# boards.net
KiCad netlist of a schematic drawn in EAGLE
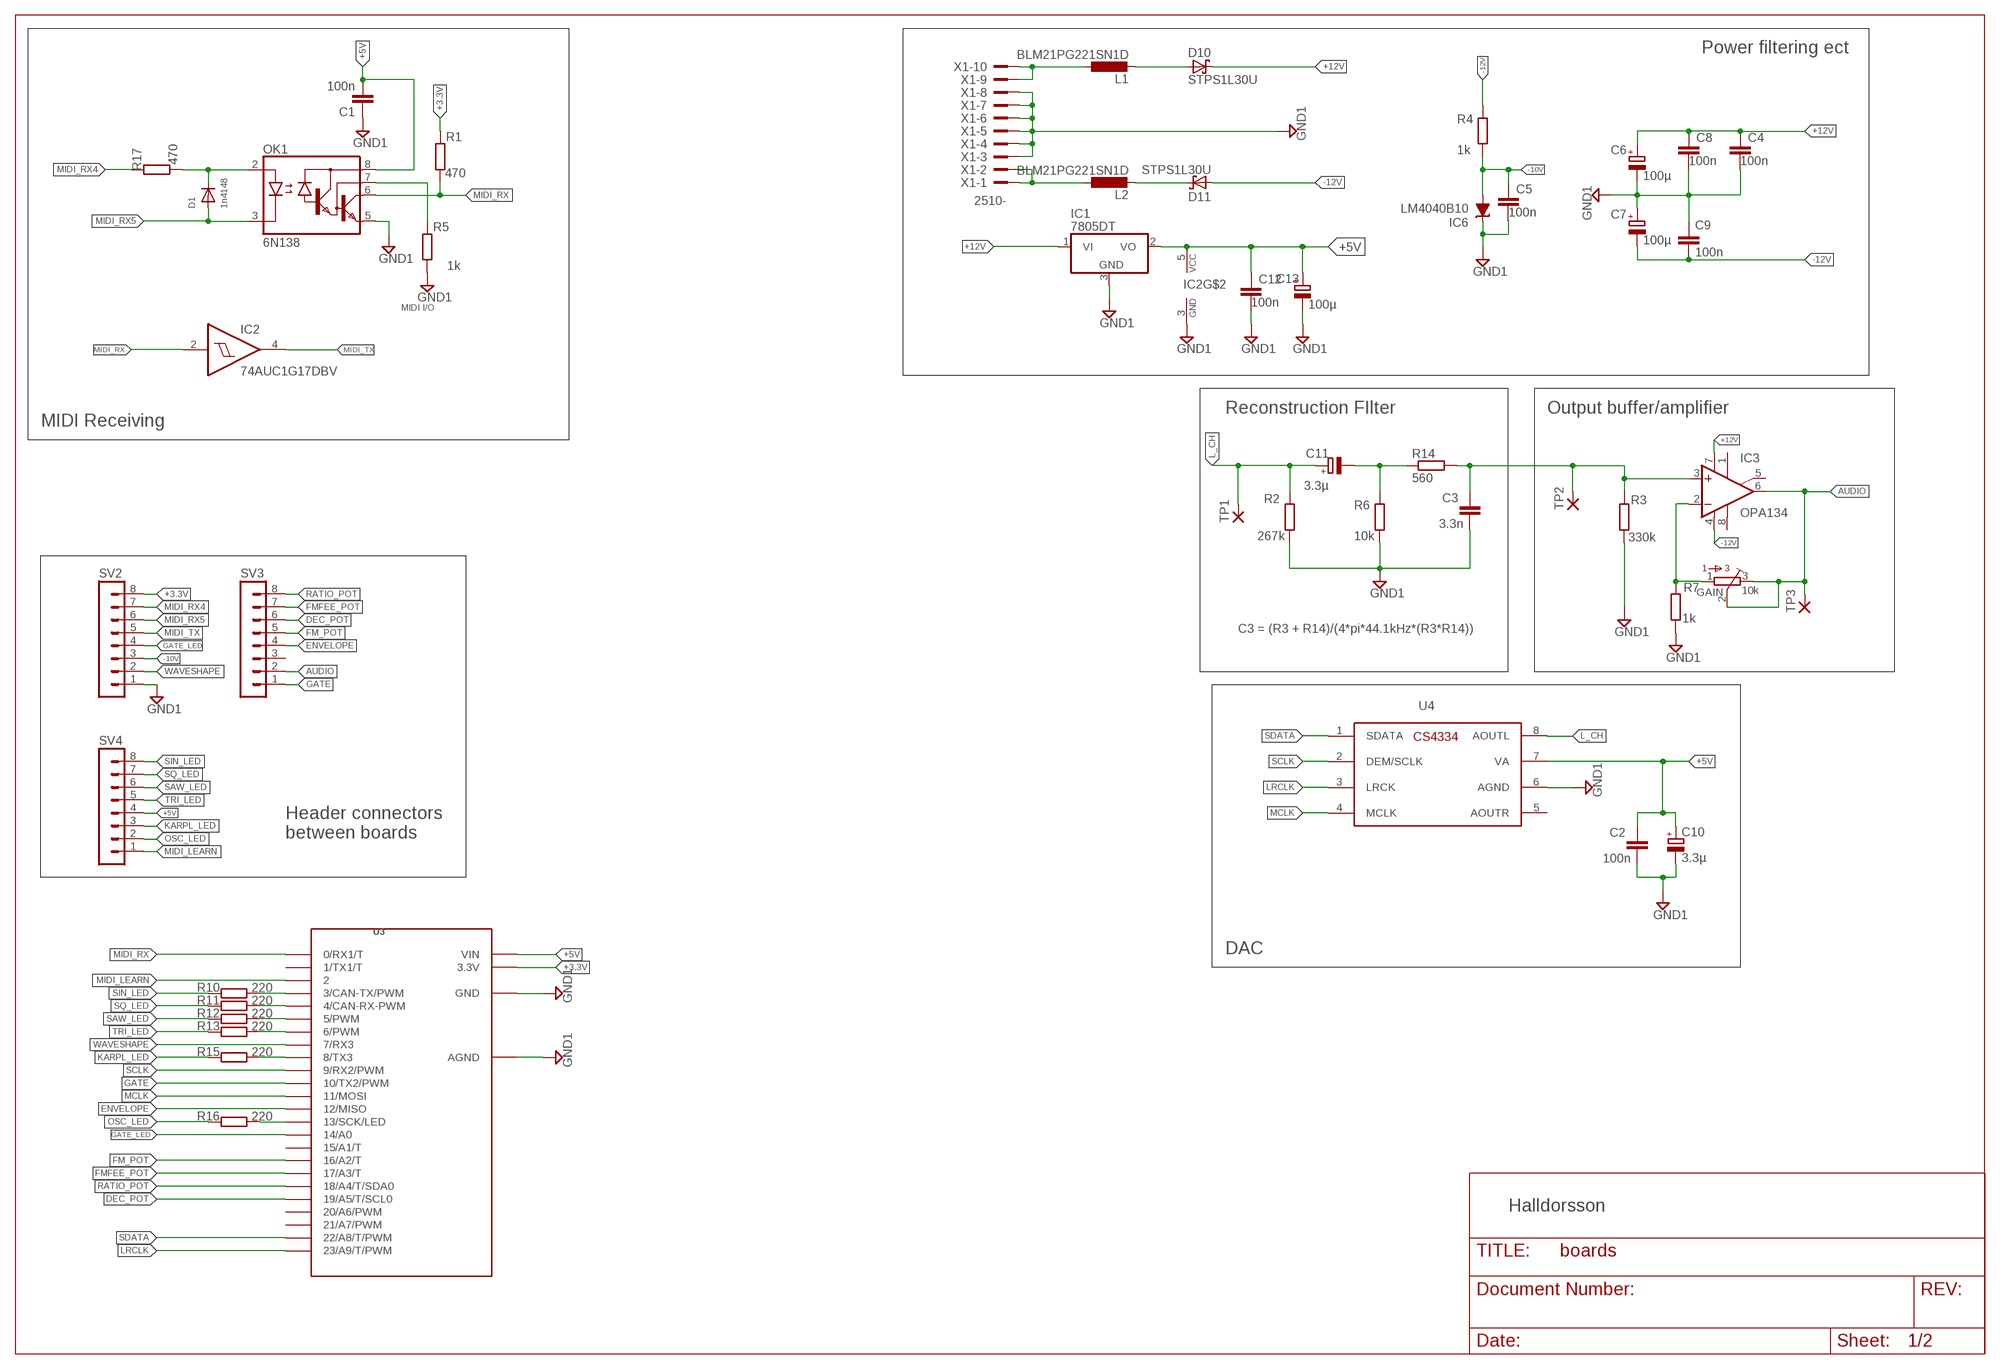
[diagram p0: schematic, sheet 1]
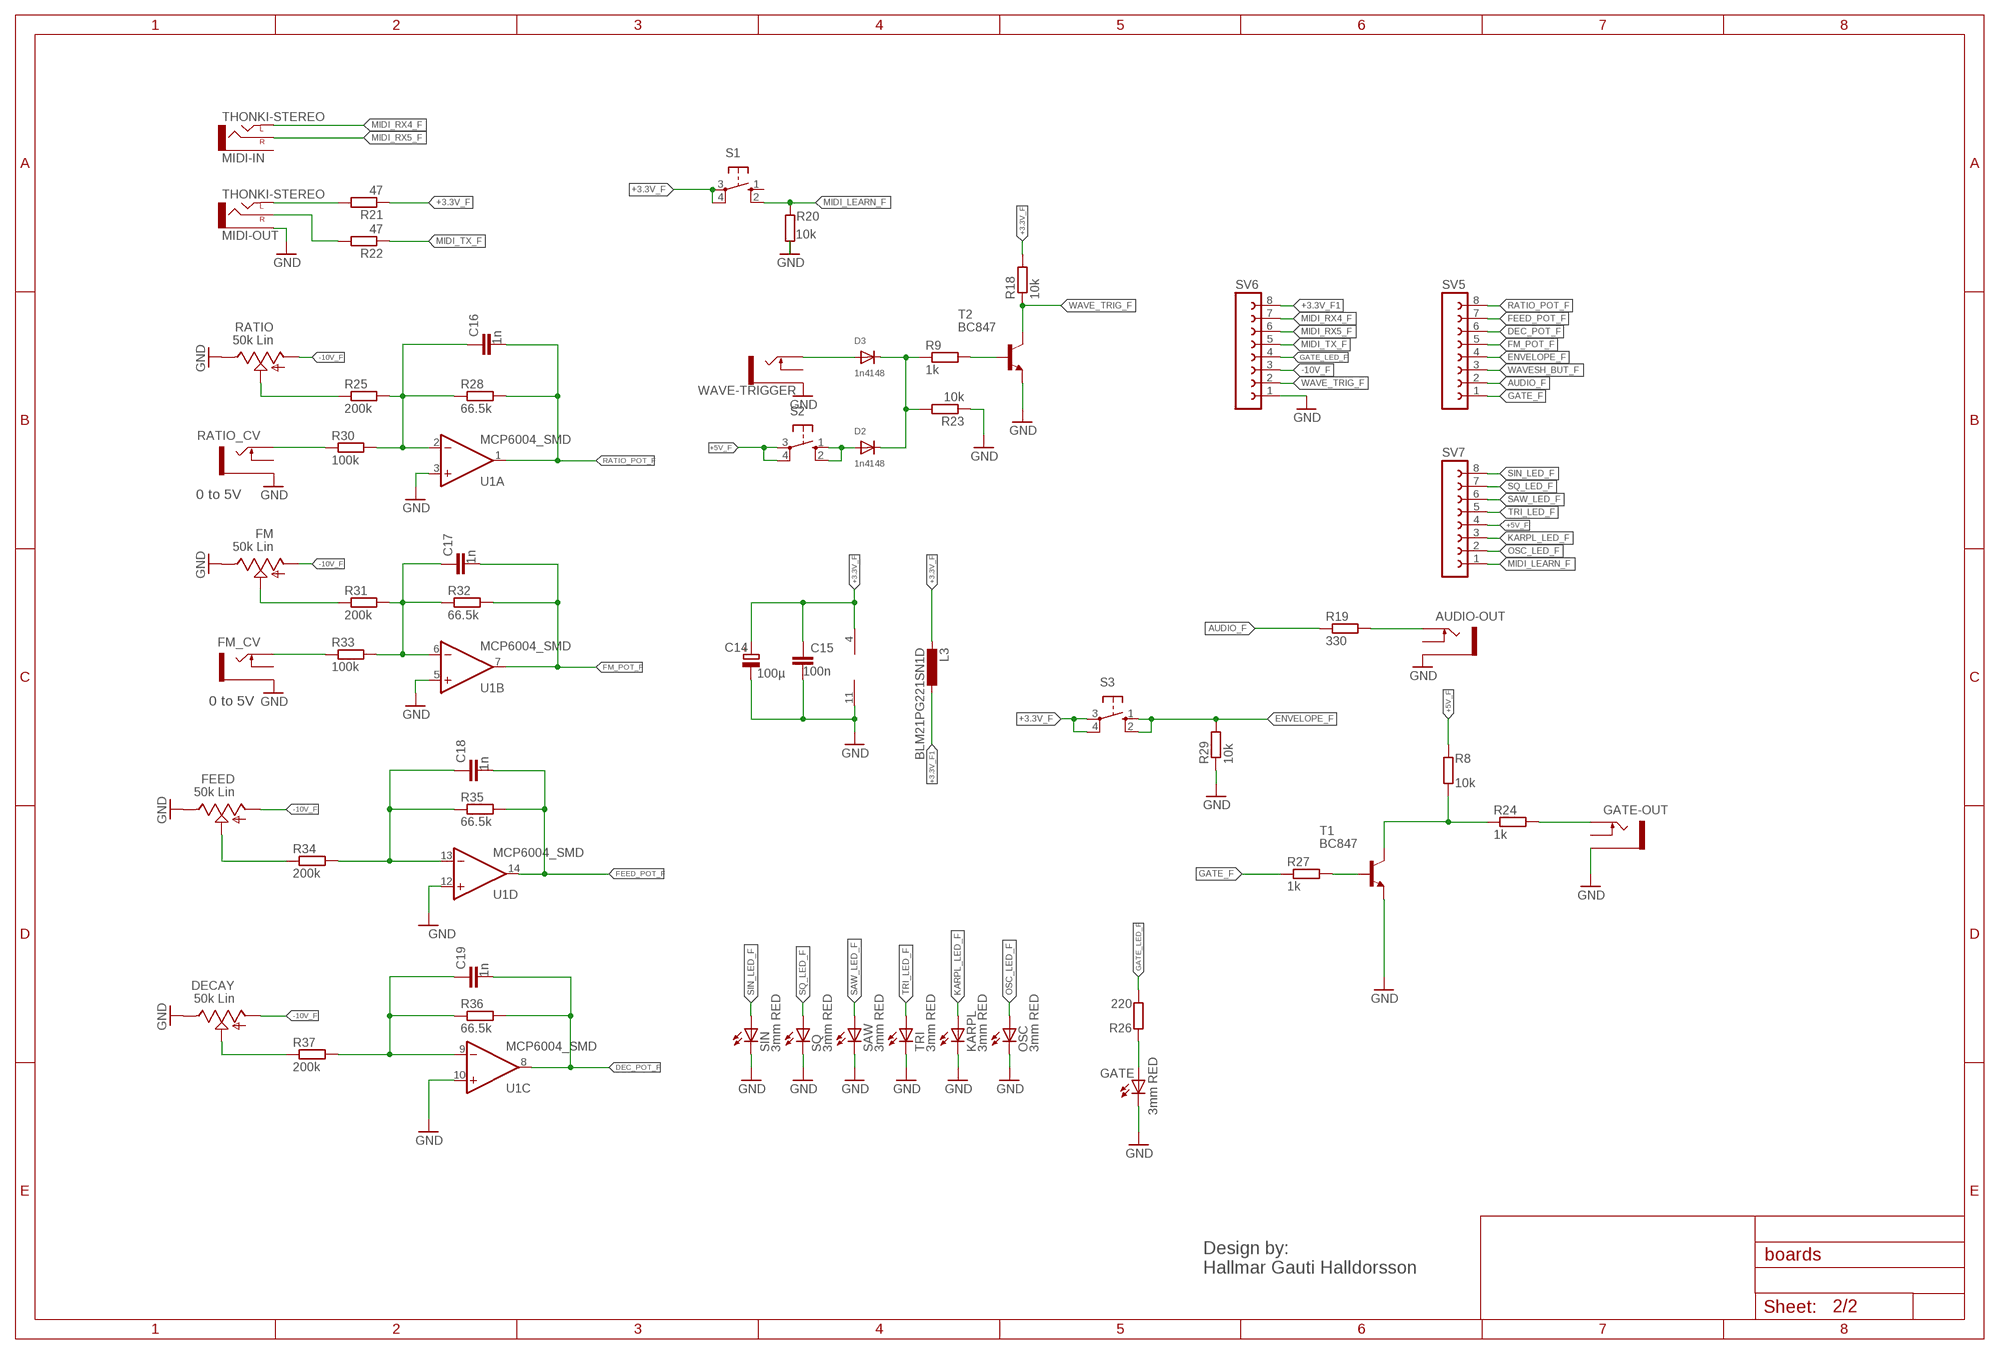
[diagram p1: schematic, sheet 2]

(export (version "E")
  (design (tool "Eeschema 10.0.6"))
  (components
    (comp (ref "C1")
      (value "100n")
      (footprint "eagle-import:C1206")
      (libsource (lib "eagle-import") (part "C-EUC1206"))
    )
    (comp (ref "C2")
      (value "100n")
      (footprint "eagle-import:C1206")
      (libsource (lib "eagle-import") (part "C-EUC1206"))
    )
    (comp (ref "C3")
      (value "3.3n")
      (footprint "eagle-import:C1206")
      (libsource (lib "eagle-import") (part "C-EUC1206"))
    )
    (comp (ref "C4")
      (value "100n")
      (footprint "eagle-import:C1206")
      (libsource (lib "eagle-import") (part "C-EUC1206"))
    )
    (comp (ref "C5")
      (value "100n")
      (footprint "eagle-import:C1206")
      (libsource (lib "eagle-import") (part "C-EUC1206"))
    )
    (comp (ref "C6")
      (value "100µ")
      (footprint "eagle-import:153CLV-0505")
      (libsource (lib "eagle-import") (part "CPOL-EU153CLV-0505"))
    )
    (comp (ref "C7")
      (value "100µ")
      (footprint "eagle-import:153CLV-0505")
      (libsource (lib "eagle-import") (part "CPOL-EU153CLV-0505"))
    )
    (comp (ref "C8")
      (value "100n")
      (footprint "eagle-import:C1206")
      (libsource (lib "eagle-import") (part "C-EUC1206"))
    )
    (comp (ref "C9")
      (value "100n")
      (footprint "eagle-import:C1206")
      (libsource (lib "eagle-import") (part "C-EUC1206"))
    )
    (comp (ref "C10")
      (value "3.3µ")
      (footprint "eagle-import:153CLV-0405")
      (libsource (lib "eagle-import") (part "CPOL-EU153CLV-0405"))
    )
    (comp (ref "C11")
      (value "3.3µ")
      (footprint "eagle-import:153CLV-0405")
      (libsource (lib "eagle-import") (part "CPOL-EU153CLV-0405"))
    )
    (comp (ref "C12")
      (value "100n")
      (footprint "eagle-import:C1206")
      (libsource (lib "eagle-import") (part "C-EUC1206"))
    )
    (comp (ref "C13")
      (value "100µ")
      (footprint "eagle-import:153CLV-0505")
      (libsource (lib "eagle-import") (part "CPOL-EU153CLV-0505"))
    )
    (comp (ref "D1")
      (value "1n4148")
      (footprint "eagle-import:SOD-123")
      (libsource (lib "eagle-import") (part "DIODESOD-123"))
    )
    (comp (ref "D10")
      (value "STPS1L30U")
      (footprint "eagle-import:SMB")
      (libsource (lib "eagle-import") (part "MBRS130LT3"))
    )
    (comp (ref "D11")
      (value "STPS1L30U")
      (footprint "eagle-import:SMB")
      (libsource (lib "eagle-import") (part "MBRS130LT3"))
    )
    (comp (ref "GAIN")
      (value "10k")
      (footprint "eagle-import:BOURNS_3362P_TRIMMER")
      (libsource (lib "eagle-import") (part "BOURNS_3362P_TRIMMERP"))
    )
    (comp (ref "IC1")
      (value "7805DT")
      (footprint "eagle-import:TO252")
      (libsource (lib "eagle-import") (part "78DT05"))
    )
    (comp (ref "IC2")
      (value "74AUC1G17DBV")
      (footprint "eagle-import:SOT23-5")
      (libsource (lib "eagle-import") (part "741G17DBVAUC"))
    )
    (comp (ref "IC3")
      (value "OPA134")
      (footprint "eagle-import:SO08")
      (libsource (lib "eagle-import") (part "TL071D"))
    )
    (comp (ref "IC6")
      (value "LM4040B10")
      (footprint "eagle-import:DBZ_R-PDSO-G3")
      (fields (field (name "MPN") "LM4041B12IDBZR"))
      (libsource (lib "eagle-import") (part "LM4041DBZB12"))
    )
    (comp (ref "L1")
      (value "BLM21PG221SN1D")
      (footprint "eagle-import:L2012C")
      (libsource (lib "eagle-import") (part "L-EUL2012C"))
    )
    (comp (ref "L2")
      (value "BLM21PG221SN1D")
      (footprint "eagle-import:L2012C")
      (libsource (lib "eagle-import") (part "L-EUL2012C"))
    )
    (comp (ref "OK1")
      (value "6N138")
      (footprint "eagle-import:DIL08")
      (fields (field (name "MF") "VISHAY/TELEFUNKEN"))
      (libsource (lib "eagle-import") (part "6N138"))
    )
    (comp (ref "R1")
      (value "470")
      (footprint "eagle-import:M1206")
      (libsource (lib "eagle-import") (part "R-EU_M1206"))
    )
    (comp (ref "R2")
      (value "267k")
      (footprint "eagle-import:M1206")
      (libsource (lib "eagle-import") (part "R-EU_M1206"))
    )
    (comp (ref "R3")
      (value "330k")
      (footprint "eagle-import:M1206")
      (libsource (lib "eagle-import") (part "R-EU_M1206"))
    )
    (comp (ref "R4")
      (value "1k")
      (footprint "eagle-import:M1206")
      (libsource (lib "eagle-import") (part "R-EU_M1206"))
    )
    (comp (ref "R5")
      (value "1k")
      (footprint "eagle-import:M1206")
      (libsource (lib "eagle-import") (part "R-EU_M1206"))
    )
    (comp (ref "R6")
      (value "10k")
      (footprint "eagle-import:M1206")
      (libsource (lib "eagle-import") (part "R-EU_M1206"))
    )
    (comp (ref "R7")
      (value "1k")
      (footprint "eagle-import:M1206")
      (libsource (lib "eagle-import") (part "R-EU_M1206"))
    )
    (comp (ref "R10")
      (value "220")
      (footprint "eagle-import:M1206")
      (libsource (lib "eagle-import") (part "R-EU_M1206"))
    )
    (comp (ref "R11")
      (value "220")
      (footprint "eagle-import:M1206")
      (libsource (lib "eagle-import") (part "R-EU_M1206"))
    )
    (comp (ref "R12")
      (value "220")
      (footprint "eagle-import:M1206")
      (libsource (lib "eagle-import") (part "R-EU_M1206"))
    )
    (comp (ref "R13")
      (value "220")
      (footprint "eagle-import:M1206")
      (libsource (lib "eagle-import") (part "R-EU_M1206"))
    )
    (comp (ref "R14")
      (value "560")
      (footprint "eagle-import:M1206")
      (libsource (lib "eagle-import") (part "R-EU_M1206"))
    )
    (comp (ref "R15")
      (value "220")
      (footprint "eagle-import:M1206")
      (libsource (lib "eagle-import") (part "R-EU_M1206"))
    )
    (comp (ref "R16")
      (value "220")
      (footprint "eagle-import:M1206")
      (libsource (lib "eagle-import") (part "R-EU_M1206"))
    )
    (comp (ref "R17")
      (value "470")
      (footprint "eagle-import:M1206")
      (libsource (lib "eagle-import") (part "R-EU_M1206"))
    )
    (comp (ref "SV2")
      (value "MA08-1")
      (footprint "eagle-import:MA08-1")
      (libsource (lib "eagle-import") (part "MA08-1"))
    )
    (comp (ref "SV3")
      (value "MA08-1")
      (footprint "eagle-import:MA08-1")
      (libsource (lib "eagle-import") (part "MA08-1"))
    )
    (comp (ref "SV4")
      (value "MA08-1")
      (footprint "eagle-import:MA08-1")
      (libsource (lib "eagle-import") (part "MA08-1"))
    )
    (comp (ref "TP1")
      (value "2,54/1,0")
      (footprint "eagle-import:2,54_1,0")
      (libsource (lib "eagle-import") (part "2,54/1,0"))
    )
    (comp (ref "TP2")
      (value "2,54/1,0")
      (footprint "eagle-import:2,54_1,0")
      (libsource (lib "eagle-import") (part "2,54/1,0"))
    )
    (comp (ref "TP3")
      (value "2,54/1,0")
      (footprint "eagle-import:2,54_1,0")
      (libsource (lib "eagle-import") (part "2,54/1,0"))
    )
    (comp (ref "U3")
      (value "TEENSY3.2.BAREBONES")
      (footprint "eagle-import:TEENSY3.2_BAREBONES")
      (libsource (lib "eagle-import") (part "TEENSY3.2.BAREBONES"))
    )
    (comp (ref "U4")
      (value "CS4334")
      (footprint "eagle-import:SOIC127P600X175-8N")
      (libsource (lib "eagle-import") (part "CS4334"))
    )
    (comp (ref "X1")
      (value "2510-")
      (footprint "eagle-import:PAK100_2500-10")
      (fields (field (name "MF") "3M") (field (name "MPN") "2510-6002UB"))
      (libsource (lib "eagle-import") (part "2510-"))
    )
    (comp (ref "AUDIO-OUT")
      (value "THONKICONNNEW")
      (footprint "eagle-import:WQP-PJ301M-12_JACK")
      (libsource (lib "eagle-import") (part "THONKICONNNEW"))
    )
    (comp (ref "C14")
      (value "100µ")
      (footprint "eagle-import:153CLV-0505")
      (libsource (lib "eagle-import") (part "CPOL-EU153CLV-0505"))
    )
    (comp (ref "C15")
      (value "100n")
      (footprint "eagle-import:C1206")
      (libsource (lib "eagle-import") (part "C-EUC1206"))
    )
    (comp (ref "C16")
      (value "1n")
      (footprint "eagle-import:C1206")
      (libsource (lib "eagle-import") (part "C-EUC1206"))
    )
    (comp (ref "C17")
      (value "1n")
      (footprint "eagle-import:C1206")
      (libsource (lib "eagle-import") (part "C-EUC1206"))
    )
    (comp (ref "C18")
      (value "1n")
      (footprint "eagle-import:C1206")
      (libsource (lib "eagle-import") (part "C-EUC1206"))
    )
    (comp (ref "C19")
      (value "1n")
      (footprint "eagle-import:C1206")
      (libsource (lib "eagle-import") (part "C-EUC1206"))
    )
    (comp (ref "D2")
      (value "1n4148")
      (footprint "eagle-import:SOD-123")
      (libsource (lib "eagle-import") (part "DIODESOD-123"))
    )
    (comp (ref "D3")
      (value "1n4148")
      (footprint "eagle-import:SOD-123")
      (libsource (lib "eagle-import") (part "DIODESOD-123"))
    )
    (comp (ref "DECAY")
      (value "50k Lin")
      (footprint "eagle-import:9MM_SNAP-IN_POT")
      (libsource (lib "eagle-import") (part "9MM_SNAP-IN_POT_"))
    )
    (comp (ref "FEED")
      (value "50k Lin")
      (footprint "eagle-import:9MM_SNAP-IN_POT")
      (libsource (lib "eagle-import") (part "9MM_SNAP-IN_POT_"))
    )
    (comp (ref "FM")
      (value "50k Lin")
      (footprint "eagle-import:9MM_SNAP-IN_POT")
      (libsource (lib "eagle-import") (part "9MM_SNAP-IN_POT_"))
    )
    (comp (ref "FM_CV")
      (value "THONKICONNNEW")
      (footprint "eagle-import:WQP-PJ301M-12_JACK")
      (libsource (lib "eagle-import") (part "THONKICONNNEW"))
    )
    (comp (ref "GATE")
      (value "3mm RED")
      (footprint "eagle-import:LED3MM")
      (libsource (lib "eagle-import") (part "LED3MM"))
    )
    (comp (ref "GATE-OUT")
      (value "THONKICONNNEW")
      (footprint "eagle-import:WQP-PJ301M-12_JACK")
      (libsource (lib "eagle-import") (part "THONKICONNNEW"))
    )
    (comp (ref "KARPL")
      (value "3mm RED")
      (footprint "eagle-import:LED3MM")
      (libsource (lib "eagle-import") (part "LED3MM"))
    )
    (comp (ref "L3")
      (value "BLM21PG221SN1D")
      (footprint "eagle-import:L2012C")
      (libsource (lib "eagle-import") (part "L-EUL2012C"))
    )
    (comp (ref "MIDI-IN")
      (value "THONKI-STEREO")
      (footprint "eagle-import:WQP-PJ366ST_JACK")
      (libsource (lib "eagle-import") (part "THONKI-STEREO"))
    )
    (comp (ref "MIDI-OUT")
      (value "THONKI-STEREO")
      (footprint "eagle-import:WQP-PJ366ST_JACK")
      (libsource (lib "eagle-import") (part "THONKI-STEREO"))
    )
    (comp (ref "OSC")
      (value "3mm RED")
      (footprint "eagle-import:LED3MM")
      (libsource (lib "eagle-import") (part "LED3MM"))
    )
    (comp (ref "R8")
      (value "10k")
      (footprint "eagle-import:M1206")
      (libsource (lib "eagle-import") (part "R-EU_M1206"))
    )
    (comp (ref "R9")
      (value "1k")
      (footprint "eagle-import:M1206")
      (libsource (lib "eagle-import") (part "R-EU_M1206"))
    )
    (comp (ref "R18")
      (value "10k")
      (footprint "eagle-import:M1206")
      (libsource (lib "eagle-import") (part "R-EU_M1206"))
    )
    (comp (ref "R19")
      (value "330")
      (footprint "eagle-import:M1206")
      (libsource (lib "eagle-import") (part "R-EU_M1206"))
    )
    (comp (ref "R20")
      (value "10k")
      (footprint "eagle-import:M1206")
      (libsource (lib "eagle-import") (part "R-EU_M1206"))
    )
    (comp (ref "R21")
      (value "47")
      (footprint "eagle-import:M1206")
      (libsource (lib "eagle-import") (part "R-EU_M1206"))
    )
    (comp (ref "R22")
      (value "47")
      (footprint "eagle-import:M1206")
      (libsource (lib "eagle-import") (part "R-EU_M1206"))
    )
    (comp (ref "R23")
      (value "10k")
      (footprint "eagle-import:M1206")
      (libsource (lib "eagle-import") (part "R-EU_M1206"))
    )
    (comp (ref "R24")
      (value "1k")
      (footprint "eagle-import:M1206")
      (libsource (lib "eagle-import") (part "R-EU_M1206"))
    )
    (comp (ref "R25")
      (value "200k")
      (footprint "eagle-import:M1206")
      (libsource (lib "eagle-import") (part "R-EU_M1206"))
    )
    (comp (ref "R26")
      (value "220")
      (footprint "eagle-import:M1206")
      (libsource (lib "eagle-import") (part "R-EU_M1206"))
    )
    (comp (ref "R27")
      (value "1k")
      (footprint "eagle-import:M1206")
      (libsource (lib "eagle-import") (part "R-EU_M1206"))
    )
    (comp (ref "R28")
      (value "66.5k")
      (footprint "eagle-import:M1206")
      (libsource (lib "eagle-import") (part "R-EU_M1206"))
    )
    (comp (ref "R29")
      (value "10k")
      (footprint "eagle-import:M1206")
      (libsource (lib "eagle-import") (part "R-EU_M1206"))
    )
    (comp (ref "R30")
      (value "100k")
      (footprint "eagle-import:M1206")
      (libsource (lib "eagle-import") (part "R-EU_M1206"))
    )
    (comp (ref "R31")
      (value "200k")
      (footprint "eagle-import:M1206")
      (libsource (lib "eagle-import") (part "R-EU_M1206"))
    )
    (comp (ref "R32")
      (value "66.5k")
      (footprint "eagle-import:M1206")
      (libsource (lib "eagle-import") (part "R-EU_M1206"))
    )
    (comp (ref "R33")
      (value "100k")
      (footprint "eagle-import:M1206")
      (libsource (lib "eagle-import") (part "R-EU_M1206"))
    )
    (comp (ref "R34")
      (value "200k")
      (footprint "eagle-import:M1206")
      (libsource (lib "eagle-import") (part "R-EU_M1206"))
    )
    (comp (ref "R35")
      (value "66.5k")
      (footprint "eagle-import:M1206")
      (libsource (lib "eagle-import") (part "R-EU_M1206"))
    )
    (comp (ref "R36")
      (value "66.5k")
      (footprint "eagle-import:M1206")
      (libsource (lib "eagle-import") (part "R-EU_M1206"))
    )
    (comp (ref "R37")
      (value "200k")
      (footprint "eagle-import:M1206")
      (libsource (lib "eagle-import") (part "R-EU_M1206"))
    )
    (comp (ref "RATIO")
      (value "50k Lin")
      (footprint "eagle-import:9MM_SNAP-IN_POT")
      (libsource (lib "eagle-import") (part "9MM_SNAP-IN_POT_"))
    )
    (comp (ref "RATIO_CV")
      (value "THONKICONNNEW")
      (footprint "eagle-import:WQP-PJ301M-12_JACK")
      (libsource (lib "eagle-import") (part "THONKICONNNEW"))
    )
    (comp (ref "S1")
      (value "10-XX")
      (footprint "eagle-import:B3F-10XX")
      (fields (field (name "MPN") "B3F-1000"))
      (libsource (lib "eagle-import") (part "10-XX"))
    )
    (comp (ref "S2")
      (value "10-XX")
      (footprint "eagle-import:B3F-10XX")
      (fields (field (name "MPN") "B3F-1000"))
      (libsource (lib "eagle-import") (part "10-XX"))
    )
    (comp (ref "S3")
      (value "10-XX")
      (footprint "eagle-import:B3F-10XX")
      (fields (field (name "MPN") "B3F-1000"))
      (libsource (lib "eagle-import") (part "10-XX"))
    )
    (comp (ref "SAW")
      (value "3mm RED")
      (footprint "eagle-import:LED3MM")
      (libsource (lib "eagle-import") (part "LED3MM"))
    )
    (comp (ref "SIN")
      (value "3mm RED")
      (footprint "eagle-import:LED3MM")
      (libsource (lib "eagle-import") (part "LED3MM"))
    )
    (comp (ref "SQ")
      (value "3mm RED")
      (footprint "eagle-import:LED3MM")
      (libsource (lib "eagle-import") (part "LED3MM"))
    )
    (comp (ref "SV5")
      (value "FE08-1")
      (footprint "eagle-import:FE08")
      (libsource (lib "eagle-import") (part "FE08-1"))
    )
    (comp (ref "SV6")
      (value "FE08-1")
      (footprint "eagle-import:FE08")
      (libsource (lib "eagle-import") (part "FE08-1"))
    )
    (comp (ref "SV7")
      (value "FE08-1")
      (footprint "eagle-import:FE08")
      (libsource (lib "eagle-import") (part "FE08-1"))
    )
    (comp (ref "T1")
      (value "BC847")
      (footprint "eagle-import:SOT23")
      (libsource (lib "eagle-import") (part "BC847"))
    )
    (comp (ref "T2")
      (value "BC847")
      (footprint "eagle-import:SOT23")
      (libsource (lib "eagle-import") (part "BC847"))
    )
    (comp (ref "TRI")
      (value "3mm RED")
      (footprint "eagle-import:LED3MM")
      (libsource (lib "eagle-import") (part "LED3MM"))
    )
    (comp (ref "U1")
      (value "MCP6004_SMD")
      (footprint "eagle-import:SO14")
      (libsource (lib "eagle-import") (part "MCP6004_SMD"))
    )
    (comp (ref "WAVE-TRIGGER")
      (value "THONKICONNNEW")
      (footprint "eagle-import:WQP-PJ301M-12_JACK")
      (libsource (lib "eagle-import") (part "THONKICONNNEW"))
    )
  )
  (nets
    (net (code "1") (name "+3.3V") (class "Default")
      (node (ref "R1") (pin "2") (pinfunction "2_2") (pintype "passive"))
      (node (ref "SV2") (pin "8") (pinfunction "8_8") (pintype "passive"))
      (node (ref "U3") (pin "3.3V") (pinfunction "3.3V_3.3V") (pintype "power_in"))
    )
    (net (code "2") (name "+3.3V_F") (class "Default")
      (node (ref "C14") (pin "+") (pinfunction "+_+") (pintype "passive"))
      (node (ref "C15") (pin "1") (pinfunction "1_1") (pintype "passive"))
      (node (ref "L3") (pin "2") (pinfunction "2_2") (pintype "passive"))
      (node (ref "R18") (pin "2") (pinfunction "2_2") (pintype "passive"))
      (node (ref "R21") (pin "1") (pinfunction "1_1") (pintype "passive"))
      (node (ref "S1") (pin "3") (pinfunction "P_3") (pintype "passive"))
      (node (ref "S1") (pin "4") (pinfunction "P1_4") (pintype "passive"))
      (node (ref "S3") (pin "3") (pinfunction "P_3") (pintype "passive"))
      (node (ref "S3") (pin "4") (pinfunction "P1_4") (pintype "passive"))
      (node (ref "U1") (pin "4") (pinfunction "V+_4") (pintype "power_in"))
    )
    (net (code "3") (name "+3.3V_F1") (class "Default")
      (node (ref "L3") (pin "1") (pinfunction "1_1") (pintype "passive"))
      (node (ref "SV6") (pin "8") (pinfunction "8_8") (pintype "passive"))
    )
    (net (code "4") (name "+5V") (class "Default")
      (node (ref "C1") (pin "2") (pinfunction "2_2") (pintype "passive"))
      (node (ref "C10") (pin "+") (pinfunction "+_+") (pintype "passive"))
      (node (ref "C12") (pin "1") (pinfunction "1_1") (pintype "passive"))
      (node (ref "C13") (pin "+") (pinfunction "+_+") (pintype "passive"))
      (node (ref "C2") (pin "1") (pinfunction "1_1") (pintype "passive"))
      (node (ref "IC1") (pin "2") (pinfunction "VO_2") (pintype "passive"))
      (node (ref "IC2") (pin "5") (pinfunction "VCC_5") (pintype "power_in"))
      (node (ref "OK1") (pin "8") (pinfunction "VCC_8") (pintype "passive"))
      (node (ref "SV4") (pin "4") (pinfunction "4_4") (pintype "passive"))
      (node (ref "U3") (pin "VIN") (pinfunction "VIN_VIN") (pintype "power_in"))
      (node (ref "U4") (pin "7") (pinfunction "VA_7") (pintype "bidirectional"))
    )
    (net (code "5") (name "+5V_F") (class "Default")
      (node (ref "R8") (pin "1") (pinfunction "1_1") (pintype "passive"))
      (node (ref "S2") (pin "3") (pinfunction "P_3") (pintype "passive"))
      (node (ref "S2") (pin "4") (pinfunction "P1_4") (pintype "passive"))
      (node (ref "SV7") (pin "4") (pinfunction "4_4") (pintype "passive"))
    )
    (net (code "6") (name "+12V") (class "Default")
      (node (ref "C4") (pin "1") (pinfunction "1_1") (pintype "passive"))
      (node (ref "C6") (pin "+") (pinfunction "+_+") (pintype "passive"))
      (node (ref "C8") (pin "1") (pinfunction "1_1") (pintype "passive"))
      (node (ref "D10") (pin "C") (pinfunction "C_C") (pintype "passive"))
      (node (ref "IC1") (pin "1") (pinfunction "VI_1") (pintype "input"))
      (node (ref "IC3") (pin "7") (pinfunction "V+_7") (pintype "power_in"))
    )
    (net (code "7") (name "-10V") (class "Default")
      (node (ref "C5") (pin "1") (pinfunction "1_1") (pintype "passive"))
      (node (ref "IC6") (pin "2") (pinfunction "A_2") (pintype "passive"))
      (node (ref "R4") (pin "2") (pinfunction "2_2") (pintype "passive"))
      (node (ref "SV2") (pin "3") (pinfunction "3_3") (pintype "passive"))
    )
    (net (code "8") (name "-10V_F") (class "Default")
      (node (ref "DECAY") (pin "1") (pinfunction "A_1") (pintype "passive"))
      (node (ref "FEED") (pin "1") (pinfunction "A_1") (pintype "passive"))
      (node (ref "FM") (pin "1") (pinfunction "A_1") (pintype "passive"))
      (node (ref "RATIO") (pin "1") (pinfunction "A_1") (pintype "passive"))
      (node (ref "SV6") (pin "3") (pinfunction "3_3") (pintype "passive"))
    )
    (net (code "9") (name "-12V") (class "Default")
      (node (ref "C7") (pin "-") (pinfunction "-_-") (pintype "passive"))
      (node (ref "C9") (pin "2") (pinfunction "2_2") (pintype "passive"))
      (node (ref "D11") (pin "A") (pinfunction "A_A") (pintype "passive"))
      (node (ref "IC3") (pin "4") (pinfunction "V-_4") (pintype "power_in"))
      (node (ref "R4") (pin "1") (pinfunction "1_1") (pintype "passive"))
    )
    (net (code "10") (name "AUDIO") (class "Default")
      (node (ref "GAIN") (pin "2") (pinfunction "2_2") (pintype "passive"))
      (node (ref "GAIN") (pin "3") (pinfunction "3_3") (pintype "passive"))
      (node (ref "IC3") (pin "6") (pinfunction "OUT_6") (pintype "output"))
      (node (ref "SV3") (pin "2") (pinfunction "2_2") (pintype "passive"))
      (node (ref "TP3") (pin "1") (pinfunction "P_1") (pintype "passive"))
    )
    (net (code "11") (name "AUDIO_F") (class "Default")
      (node (ref "R19") (pin "1") (pinfunction "1_1") (pintype "passive"))
      (node (ref "SV5") (pin "2") (pinfunction "2_2") (pintype "passive"))
    )
    (net (code "12") (name "DEC_POT") (class "Default")
      (node (ref "SV3") (pin "6") (pinfunction "6_6") (pintype "passive"))
      (node (ref "U3") (pin "19/A5") (pinfunction "19/A5/T/SCL0_19/A5") (pintype "bidirectional"))
    )
    (net (code "13") (name "DEC_POT_F") (class "Default")
      (node (ref "C19") (pin "2") (pinfunction "2_2") (pintype "passive"))
      (node (ref "R36") (pin "2") (pinfunction "2_2") (pintype "passive"))
      (node (ref "SV5") (pin "6") (pinfunction "6_6") (pintype "passive"))
      (node (ref "U1") (pin "8") (pinfunction "OUT_8") (pintype "output"))
    )
    (net (code "14") (name "ENVELOPE") (class "Default")
      (node (ref "SV3") (pin "4") (pinfunction "4_4") (pintype "passive"))
      (node (ref "U3") (pin "12") (pinfunction "12/MISO_12") (pintype "bidirectional"))
    )
    (net (code "15") (name "ENVELOPE_F") (class "Default")
      (node (ref "R29") (pin "2") (pinfunction "2_2") (pintype "passive"))
      (node (ref "S3") (pin "1") (pinfunction "S_1") (pintype "passive"))
      (node (ref "S3") (pin "2") (pinfunction "S1_2") (pintype "passive"))
      (node (ref "SV5") (pin "4") (pinfunction "4_4") (pintype "passive"))
    )
    (net (code "16") (name "FEED_POT_F") (class "Default")
      (node (ref "C18") (pin "2") (pinfunction "2_2") (pintype "passive"))
      (node (ref "R35") (pin "2") (pinfunction "2_2") (pintype "passive"))
      (node (ref "SV5") (pin "7") (pinfunction "7_7") (pintype "passive"))
      (node (ref "U1") (pin "14") (pinfunction "OUT_14") (pintype "output"))
    )
    (net (code "17") (name "FMFEE_POT") (class "Default")
      (node (ref "SV3") (pin "7") (pinfunction "7_7") (pintype "passive"))
      (node (ref "U3") (pin "17/A3") (pinfunction "17/A3/T_17/A3") (pintype "bidirectional"))
    )
    (net (code "18") (name "FM_POT") (class "Default")
      (node (ref "SV3") (pin "5") (pinfunction "5_5") (pintype "passive"))
      (node (ref "U3") (pin "16/A2") (pinfunction "16/A2/T_16/A2") (pintype "bidirectional"))
    )
    (net (code "19") (name "FM_POT_F") (class "Default")
      (node (ref "C17") (pin "2") (pinfunction "2_2") (pintype "passive"))
      (node (ref "R32") (pin "2") (pinfunction "2_2") (pintype "passive"))
      (node (ref "SV5") (pin "5") (pinfunction "5_5") (pintype "passive"))
      (node (ref "U1") (pin "7") (pinfunction "OUT_7") (pintype "output"))
    )
    (net (code "20") (name "GATE") (class "Default")
      (node (ref "SV3") (pin "1") (pinfunction "1_1") (pintype "passive"))
      (node (ref "U3") (pin "10") (pinfunction "10/TX2/PWM_10") (pintype "bidirectional"))
    )
    (net (code "21") (name "GATE_F") (class "Default")
      (node (ref "R27") (pin "1") (pinfunction "1_1") (pintype "passive"))
      (node (ref "SV5") (pin "1") (pinfunction "1_1") (pintype "passive"))
    )
    (net (code "22") (name "GATE_LED") (class "Default")
      (node (ref "SV2") (pin "4") (pinfunction "4_4") (pintype "passive"))
      (node (ref "U3") (pin "14/A0") (pinfunction "14/A0_14/A0") (pintype "bidirectional"))
    )
    (net (code "23") (name "GATE_LED_F") (class "Default")
      (node (ref "R26") (pin "2") (pinfunction "2_2") (pintype "passive"))
      (node (ref "SV6") (pin "4") (pinfunction "4_4") (pintype "passive"))
    )
    (net (code "24") (name "GND") (class "Default")
      (node (ref "AUDIO-OUT") (pin "P$3_SLEEVE") (pinfunction "SLEEVE_P$3_SLEEVE") (pintype "passive"))
      (node (ref "C14") (pin "-") (pinfunction "-_-") (pintype "passive"))
      (node (ref "C15") (pin "2") (pinfunction "2_2") (pintype "passive"))
      (node (ref "DECAY") (pin "3") (pinfunction "E_3") (pintype "passive"))
      (node (ref "FEED") (pin "3") (pinfunction "E_3") (pintype "passive"))
      (node (ref "FM") (pin "3") (pinfunction "E_3") (pintype "passive"))
      (node (ref "FM_CV") (pin "P$3_SLEEVE") (pinfunction "SLEEVE_P$3_SLEEVE") (pintype "passive"))
      (node (ref "GATE") (pin "K") (pinfunction "C_K") (pintype "passive"))
      (node (ref "GATE-OUT") (pin "P$3_SLEEVE") (pinfunction "SLEEVE_P$3_SLEEVE") (pintype "passive"))
      (node (ref "KARPL") (pin "K") (pinfunction "C_K") (pintype "passive"))
      (node (ref "MIDI-OUT") (pin "P$3_SLEEVE") (pinfunction "SLEEVE_P$3_SLEEVE") (pintype "bidirectional"))
      (node (ref "OSC") (pin "K") (pinfunction "C_K") (pintype "passive"))
      (node (ref "R20") (pin "2") (pinfunction "2_2") (pintype "passive"))
      (node (ref "R23") (pin "1") (pinfunction "1_1") (pintype "passive"))
      (node (ref "R29") (pin "1") (pinfunction "1_1") (pintype "passive"))
      (node (ref "RATIO") (pin "3") (pinfunction "E_3") (pintype "passive"))
      (node (ref "RATIO_CV") (pin "P$3_SLEEVE") (pinfunction "SLEEVE_P$3_SLEEVE") (pintype "passive"))
      (node (ref "SAW") (pin "K") (pinfunction "C_K") (pintype "passive"))
      (node (ref "SIN") (pin "K") (pinfunction "C_K") (pintype "passive"))
      (node (ref "SQ") (pin "K") (pinfunction "C_K") (pintype "passive"))
      (node (ref "SV6") (pin "1") (pinfunction "1_1") (pintype "passive"))
      (node (ref "T1") (pin "2") (pinfunction "E_2") (pintype "passive"))
      (node (ref "T2") (pin "2") (pinfunction "E_2") (pintype "passive"))
      (node (ref "TRI") (pin "K") (pinfunction "C_K") (pintype "passive"))
      (node (ref "U1") (pin "10") (pinfunction "+IN_10") (pintype "input"))
      (node (ref "U1") (pin "11") (pinfunction "V-_11") (pintype "power_in"))
      (node (ref "U1") (pin "12") (pinfunction "+IN_12") (pintype "input"))
      (node (ref "U1") (pin "3") (pinfunction "+IN_3") (pintype "input"))
      (node (ref "U1") (pin "5") (pinfunction "+IN_5") (pintype "input"))
      (node (ref "WAVE-TRIGGER") (pin "P$3_SLEEVE") (pinfunction "SLEEVE_P$3_SLEEVE") (pintype "passive"))
    )
    (net (code "25") (name "GND1") (class "Default")
      (node (ref "C1") (pin "1") (pinfunction "1_1") (pintype "passive"))
      (node (ref "C10") (pin "-") (pinfunction "-_-") (pintype "passive"))
      (node (ref "C12") (pin "2") (pinfunction "2_2") (pintype "passive"))
      (node (ref "C13") (pin "-") (pinfunction "-_-") (pintype "passive"))
      (node (ref "C2") (pin "2") (pinfunction "2_2") (pintype "passive"))
      (node (ref "C3") (pin "2") (pinfunction "2_2") (pintype "passive"))
      (node (ref "C4") (pin "2") (pinfunction "2_2") (pintype "passive"))
      (node (ref "C5") (pin "2") (pinfunction "2_2") (pintype "passive"))
      (node (ref "C6") (pin "-") (pinfunction "-_-") (pintype "passive"))
      (node (ref "C7") (pin "+") (pinfunction "+_+") (pintype "passive"))
      (node (ref "C8") (pin "2") (pinfunction "2_2") (pintype "passive"))
      (node (ref "C9") (pin "1") (pinfunction "1_1") (pintype "passive"))
      (node (ref "IC1") (pin "3") (pinfunction "GND_3") (pintype "passive"))
      (node (ref "IC2") (pin "3") (pinfunction "GND_3") (pintype "power_in"))
      (node (ref "IC6") (pin "1") (pinfunction "C_1") (pintype "passive"))
      (node (ref "OK1") (pin "5") (pinfunction "GND_5") (pintype "passive"))
      (node (ref "R2") (pin "2") (pinfunction "2_2") (pintype "passive"))
      (node (ref "R3") (pin "2") (pinfunction "2_2") (pintype "passive"))
      (node (ref "R5") (pin "1") (pinfunction "1_1") (pintype "passive"))
      (node (ref "R6") (pin "2") (pinfunction "2_2") (pintype "passive"))
      (node (ref "R7") (pin "2") (pinfunction "2_2") (pintype "passive"))
      (node (ref "SV2") (pin "1") (pinfunction "1_1") (pintype "passive"))
      (node (ref "U3") (pin "AGND") (pinfunction "AGND_AGND") (pintype "power_in"))
      (node (ref "U3") (pin "GND") (pinfunction "GND_GND") (pintype "power_in"))
      (node (ref "U4") (pin "6") (pinfunction "AGND_6") (pintype "bidirectional"))
      (node (ref "X1") (pin "3") (pinfunction "KL_3") (pintype "passive"))
      (node (ref "X1") (pin "4") (pinfunction "KL_4") (pintype "passive"))
      (node (ref "X1") (pin "5") (pinfunction "KL_5") (pintype "passive"))
      (node (ref "X1") (pin "6") (pinfunction "KL_6") (pintype "passive"))
      (node (ref "X1") (pin "7") (pinfunction "KL_7") (pintype "passive"))
      (node (ref "X1") (pin "8") (pinfunction "KL_8") (pintype "passive"))
    )
    (net (code "26") (name "KARPL_LED") (class "Default")
      (node (ref "R15") (pin "2") (pinfunction "2_2") (pintype "passive"))
      (node (ref "SV4") (pin "3") (pinfunction "3_3") (pintype "passive"))
    )
    (net (code "27") (name "KARPL_LED_F") (class "Default")
      (node (ref "KARPL") (pin "A") (pinfunction "A_A") (pintype "passive"))
      (node (ref "SV7") (pin "3") (pinfunction "3_3") (pintype "passive"))
    )
    (net (code "28") (name "LRCLK") (class "Default")
      (node (ref "U3") (pin "23/A9") (pinfunction "23/A9/T/PWM_23/A9") (pintype "bidirectional"))
      (node (ref "U4") (pin "3") (pinfunction "LRCK_3") (pintype "bidirectional"))
    )
    (net (code "29") (name "L_CH") (class "Default")
      (node (ref "C11") (pin "+") (pinfunction "+_+") (pintype "passive"))
      (node (ref "R2") (pin "1") (pinfunction "1_1") (pintype "passive"))
      (node (ref "TP1") (pin "1") (pinfunction "P_1") (pintype "passive"))
      (node (ref "U4") (pin "8") (pinfunction "AOUTL_8") (pintype "bidirectional"))
    )
    (net (code "30") (name "MCLK") (class "Default")
      (node (ref "U3") (pin "11") (pinfunction "11/MOSI_11") (pintype "bidirectional"))
      (node (ref "U4") (pin "4") (pinfunction "MCLK_4") (pintype "bidirectional"))
    )
    (net (code "31") (name "MIDI_LEARN") (class "Default")
      (node (ref "SV4") (pin "1") (pinfunction "1_1") (pintype "passive"))
      (node (ref "U3") (pin "2") (pinfunction "2_2") (pintype "bidirectional"))
    )
    (net (code "32") (name "MIDI_LEARN_F") (class "Default")
      (node (ref "R20") (pin "1") (pinfunction "1_1") (pintype "passive"))
      (node (ref "S1") (pin "2") (pinfunction "S1_2") (pintype "passive"))
      (node (ref "SV7") (pin "1") (pinfunction "1_1") (pintype "passive"))
    )
    (net (code "33") (name "MIDI_RX") (class "Default")
      (node (ref "IC2") (pin "2") (pinfunction "I_2") (pintype "input"))
      (node (ref "OK1") (pin "6") (pinfunction "VO_6") (pintype "passive"))
      (node (ref "R1") (pin "1") (pinfunction "1_1") (pintype "passive"))
      (node (ref "U3") (pin "0") (pinfunction "0/RX1/T_0") (pintype "bidirectional"))
    )
    (net (code "34") (name "MIDI_RX4") (class "Default")
      (node (ref "R17") (pin "2") (pinfunction "2_2") (pintype "passive"))
      (node (ref "SV2") (pin "7") (pinfunction "7_7") (pintype "passive"))
    )
    (net (code "35") (name "MIDI_RX4_F") (class "Default")
      (node (ref "MIDI-IN") (pin "P$1_TIP") (pinfunction "LEFT_P$1_TIP") (pintype "bidirectional"))
      (node (ref "SV6") (pin "7") (pinfunction "7_7") (pintype "passive"))
    )
    (net (code "36") (name "MIDI_RX5") (class "Default")
      (node (ref "D1") (pin "A") (pinfunction "A_A") (pintype "passive"))
      (node (ref "OK1") (pin "3") (pinfunction "C_3") (pintype "passive"))
      (node (ref "SV2") (pin "6") (pinfunction "6_6") (pintype "passive"))
    )
    (net (code "37") (name "MIDI_RX5_F") (class "Default")
      (node (ref "MIDI-IN") (pin "P$2_SWITCH") (pinfunction "RIGHT_P$2_SWITCH") (pintype "bidirectional"))
      (node (ref "SV6") (pin "6") (pinfunction "6_6") (pintype "passive"))
    )
    (net (code "38") (name "MIDI_TX") (class "Default")
      (node (ref "IC2") (pin "4") (pinfunction "O_4") (pintype "output"))
      (node (ref "SV2") (pin "5") (pinfunction "5_5") (pintype "passive"))
    )
    (net (code "39") (name "MIDI_TX_F") (class "Default")
      (node (ref "R22") (pin "1") (pinfunction "1_1") (pintype "passive"))
      (node (ref "SV6") (pin "5") (pinfunction "5_5") (pintype "passive"))
    )
    (net (code "40") (name "Net-(AUDIO-OUT-TIP)") (class "Default")
      (node (ref "AUDIO-OUT") (pin "P$1_TIP") (pinfunction "TIP_P$1_TIP") (pintype "passive"))
      (node (ref "R19") (pin "2") (pinfunction "2_2") (pintype "passive"))
    )
    (net (code "41") (name "Net-(C11-Pad-)") (class "Default")
      (node (ref "C11") (pin "-") (pinfunction "-_-") (pintype "passive"))
      (node (ref "R14") (pin "1") (pinfunction "1_1") (pintype "passive"))
      (node (ref "R6") (pin "1") (pinfunction "1_1") (pintype "passive"))
    )
    (net (code "42") (name "Net-(D2-PadC)") (class "Default")
      (node (ref "D2") (pin "C") (pinfunction "C_C") (pintype "passive"))
      (node (ref "D3") (pin "C") (pinfunction "C_C") (pintype "passive"))
      (node (ref "R23") (pin "2") (pinfunction "2_2") (pintype "passive"))
      (node (ref "R9") (pin "1") (pinfunction "1_1") (pintype "passive"))
    )
    (net (code "43") (name "Net-(D10-PadA)") (class "Default")
      (node (ref "D10") (pin "A") (pinfunction "A_A") (pintype "passive"))
      (node (ref "L1") (pin "2") (pinfunction "2_2") (pintype "passive"))
    )
    (net (code "44") (name "Net-(D11-PadC)") (class "Default")
      (node (ref "D11") (pin "C") (pinfunction "C_C") (pintype "passive"))
      (node (ref "L2") (pin "2") (pinfunction "2_2") (pintype "passive"))
    )
    (net (code "45") (name "Net-(DECAY-S)") (class "Default")
      (node (ref "DECAY") (pin "2") (pinfunction "S_2") (pintype "passive"))
      (node (ref "R37") (pin "1") (pinfunction "1_1") (pintype "passive"))
    )
    (net (code "46") (name "Net-(FEED-S)") (class "Default")
      (node (ref "FEED") (pin "2") (pinfunction "S_2") (pintype "passive"))
      (node (ref "R34") (pin "1") (pinfunction "1_1") (pintype "passive"))
    )
    (net (code "47") (name "Net-(FM-S)") (class "Default")
      (node (ref "FM") (pin "2") (pinfunction "S_2") (pintype "passive"))
      (node (ref "R31") (pin "1") (pinfunction "1_1") (pintype "passive"))
    )
    (net (code "48") (name "Net-(FM_CV-TIP)") (class "Default")
      (node (ref "FM_CV") (pin "P$1_TIP") (pinfunction "TIP_P$1_TIP") (pintype "passive"))
      (node (ref "R33") (pin "1") (pinfunction "1_1") (pintype "passive"))
    )
    (net (code "49") (name "Net-(GATE-OUT-TIP)") (class "Default")
      (node (ref "GATE-OUT") (pin "P$1_TIP") (pinfunction "TIP_P$1_TIP") (pintype "passive"))
      (node (ref "R24") (pin "2") (pinfunction "2_2") (pintype "passive"))
    )
    (net (code "50") (name "Net-(GATE-PadA)") (class "Default")
      (node (ref "GATE") (pin "A") (pinfunction "A_A") (pintype "passive"))
      (node (ref "R26") (pin "1") (pinfunction "1_1") (pintype "passive"))
    )
    (net (code "51") (name "Net-(IC3-+IN)") (class "Default")
      (node (ref "C3") (pin "1") (pinfunction "1_1") (pintype "passive"))
      (node (ref "IC3") (pin "3") (pinfunction "+IN_3") (pintype "input"))
      (node (ref "R14") (pin "2") (pinfunction "2_2") (pintype "passive"))
      (node (ref "R3") (pin "1") (pinfunction "1_1") (pintype "passive"))
      (node (ref "TP2") (pin "1") (pinfunction "P_1") (pintype "passive"))
    )
    (net (code "52") (name "Net-(IC3--IN)") (class "Default")
      (node (ref "GAIN") (pin "1") (pinfunction "1_1") (pintype "passive"))
      (node (ref "IC3") (pin "2") (pinfunction "-IN_2") (pintype "input"))
      (node (ref "R7") (pin "1") (pinfunction "1_1") (pintype "passive"))
    )
    (net (code "53") (name "Net-(MIDI-OUT-LEFT)") (class "Default")
      (node (ref "MIDI-OUT") (pin "P$1_TIP") (pinfunction "LEFT_P$1_TIP") (pintype "bidirectional"))
      (node (ref "R21") (pin "2") (pinfunction "2_2") (pintype "passive"))
    )
    (net (code "54") (name "Net-(MIDI-OUT-RIGHT)") (class "Default")
      (node (ref "MIDI-OUT") (pin "P$2_SWITCH") (pinfunction "RIGHT_P$2_SWITCH") (pintype "bidirectional"))
      (node (ref "R22") (pin "2") (pinfunction "2_2") (pintype "passive"))
    )
    (net (code "55") (name "Net-(OK1-A)") (class "Default")
      (node (ref "D1") (pin "C") (pinfunction "C_C") (pintype "passive"))
      (node (ref "OK1") (pin "2") (pinfunction "A_2") (pintype "passive"))
      (node (ref "R17") (pin "1") (pinfunction "1_1") (pintype "passive"))
    )
    (net (code "56") (name "Net-(OK1-VB)") (class "Default")
      (node (ref "OK1") (pin "7") (pinfunction "VB_7") (pintype "passive"))
      (node (ref "R5") (pin "2") (pinfunction "2_2") (pintype "passive"))
    )
    (net (code "57") (name "Net-(RATIO-S)") (class "Default")
      (node (ref "R25") (pin "1") (pinfunction "1_1") (pintype "passive"))
      (node (ref "RATIO") (pin "2") (pinfunction "S_2") (pintype "passive"))
    )
    (net (code "58") (name "Net-(RATIO_CV-TIP)") (class "Default")
      (node (ref "R30") (pin "1") (pinfunction "1_1") (pintype "passive"))
      (node (ref "RATIO_CV") (pin "P$1_TIP") (pinfunction "TIP_P$1_TIP") (pintype "passive"))
    )
    (net (code "59") (name "Net-(S2-S)") (class "Default")
      (node (ref "D2") (pin "A") (pinfunction "A_A") (pintype "passive"))
      (node (ref "S2") (pin "1") (pinfunction "S_1") (pintype "passive"))
      (node (ref "S2") (pin "2") (pinfunction "S1_2") (pintype "passive"))
    )
    (net (code "60") (name "Net-(T1-B)") (class "Default")
      (node (ref "R27") (pin "2") (pinfunction "2_2") (pintype "passive"))
      (node (ref "T1") (pin "1") (pinfunction "B_1") (pintype "passive"))
    )
    (net (code "61") (name "Net-(T1-C)") (class "Default")
      (node (ref "R24") (pin "1") (pinfunction "1_1") (pintype "passive"))
      (node (ref "R8") (pin "2") (pinfunction "2_2") (pintype "passive"))
      (node (ref "T1") (pin "3") (pinfunction "C_3") (pintype "passive"))
    )
    (net (code "62") (name "Net-(T2-B)") (class "Default")
      (node (ref "R9") (pin "2") (pinfunction "2_2") (pintype "passive"))
      (node (ref "T2") (pin "1") (pinfunction "B_1") (pintype "passive"))
    )
    (net (code "63") (name "Net-(U1A--IN)") (class "Default")
      (node (ref "C16") (pin "1") (pinfunction "1_1") (pintype "passive"))
      (node (ref "R25") (pin "2") (pinfunction "2_2") (pintype "passive"))
      (node (ref "R28") (pin "1") (pinfunction "1_1") (pintype "passive"))
      (node (ref "R30") (pin "2") (pinfunction "2_2") (pintype "passive"))
      (node (ref "U1") (pin "2") (pinfunction "-IN_2") (pintype "input"))
    )
    (net (code "64") (name "Net-(U1B--IN)") (class "Default")
      (node (ref "C17") (pin "1") (pinfunction "1_1") (pintype "passive"))
      (node (ref "R31") (pin "2") (pinfunction "2_2") (pintype "passive"))
      (node (ref "R32") (pin "1") (pinfunction "1_1") (pintype "passive"))
      (node (ref "R33") (pin "2") (pinfunction "2_2") (pintype "passive"))
      (node (ref "U1") (pin "6") (pinfunction "-IN_6") (pintype "input"))
    )
    (net (code "65") (name "Net-(U1C--IN)") (class "Default")
      (node (ref "C19") (pin "1") (pinfunction "1_1") (pintype "passive"))
      (node (ref "R36") (pin "1") (pinfunction "1_1") (pintype "passive"))
      (node (ref "R37") (pin "2") (pinfunction "2_2") (pintype "passive"))
      (node (ref "U1") (pin "9") (pinfunction "-IN_9") (pintype "input"))
    )
    (net (code "66") (name "Net-(U1D--IN)") (class "Default")
      (node (ref "C18") (pin "1") (pinfunction "1_1") (pintype "passive"))
      (node (ref "R34") (pin "2") (pinfunction "2_2") (pintype "passive"))
      (node (ref "R35") (pin "1") (pinfunction "1_1") (pintype "passive"))
      (node (ref "U1") (pin "13") (pinfunction "-IN_13") (pintype "input"))
    )
    (net (code "67") (name "Net-(U3-3{slash}CAN-TX{slash}PWM)") (class "Default")
      (node (ref "R10") (pin "1") (pinfunction "1_1") (pintype "passive"))
      (node (ref "U3") (pin "3") (pinfunction "3/CAN-TX/PWM_3") (pintype "bidirectional"))
    )
    (net (code "68") (name "Net-(U3-4{slash}CAN-RX-PWM)") (class "Default")
      (node (ref "R11") (pin "1") (pinfunction "1_1") (pintype "passive"))
      (node (ref "U3") (pin "4") (pinfunction "4/CAN-RX-PWM_4") (pintype "bidirectional"))
    )
    (net (code "69") (name "Net-(U3-5{slash}PWM)") (class "Default")
      (node (ref "R12") (pin "1") (pinfunction "1_1") (pintype "passive"))
      (node (ref "U3") (pin "5") (pinfunction "5/PWM_5") (pintype "bidirectional"))
    )
    (net (code "70") (name "Net-(U3-6{slash}PWM)") (class "Default")
      (node (ref "R13") (pin "1") (pinfunction "1_1") (pintype "passive"))
      (node (ref "U3") (pin "6") (pinfunction "6/PWM_6") (pintype "bidirectional"))
    )
    (net (code "71") (name "Net-(U3-8{slash}TX3)") (class "Default")
      (node (ref "R15") (pin "1") (pinfunction "1_1") (pintype "passive"))
      (node (ref "U3") (pin "8") (pinfunction "8/TX3_8") (pintype "bidirectional"))
    )
    (net (code "72") (name "Net-(U3-13{slash}SCK{slash}LED)") (class "Default")
      (node (ref "R16") (pin "1") (pinfunction "1_1") (pintype "passive"))
      (node (ref "U3") (pin "13") (pinfunction "13/SCK/LED_13") (pintype "bidirectional"))
    )
    (net (code "73") (name "Net-(WAVE-TRIGGER-TIP)") (class "Default")
      (node (ref "D3") (pin "A") (pinfunction "A_A") (pintype "passive"))
      (node (ref "WAVE-TRIGGER") (pin "P$1_TIP") (pinfunction "TIP_P$1_TIP") (pintype "passive"))
    )
    (net (code "74") (name "Net-(X1A-KL)") (class "Default")
      (node (ref "L2") (pin "1") (pinfunction "1_1") (pintype "passive"))
      (node (ref "X1") (pin "1") (pinfunction "KL_1") (pintype "passive"))
      (node (ref "X1") (pin "2") (pinfunction "KL_2") (pintype "passive"))
    )
    (net (code "75") (name "Net-(X1B-KL)") (class "Default")
      (node (ref "L1") (pin "1") (pinfunction "1_1") (pintype "passive"))
      (node (ref "X1") (pin "10") (pinfunction "KL_10") (pintype "passive"))
      (node (ref "X1") (pin "9") (pinfunction "KL_9") (pintype "passive"))
    )
    (net (code "76") (name "OSC_LED") (class "Default")
      (node (ref "R16") (pin "2") (pinfunction "2_2") (pintype "passive"))
      (node (ref "SV4") (pin "2") (pinfunction "2_2") (pintype "passive"))
    )
    (net (code "77") (name "OSC_LED_F") (class "Default")
      (node (ref "OSC") (pin "A") (pinfunction "A_A") (pintype "passive"))
      (node (ref "SV7") (pin "2") (pinfunction "2_2") (pintype "passive"))
    )
    (net (code "78") (name "RATIO_POT") (class "Default")
      (node (ref "SV3") (pin "8") (pinfunction "8_8") (pintype "passive"))
      (node (ref "U3") (pin "18/A4") (pinfunction "18/A4/T/SDA0_18/A4") (pintype "bidirectional"))
    )
    (net (code "79") (name "RATIO_POT_F") (class "Default")
      (node (ref "C16") (pin "2") (pinfunction "2_2") (pintype "passive"))
      (node (ref "R28") (pin "2") (pinfunction "2_2") (pintype "passive"))
      (node (ref "SV5") (pin "8") (pinfunction "8_8") (pintype "passive"))
      (node (ref "U1") (pin "1") (pinfunction "OUT_1") (pintype "output"))
    )
    (net (code "80") (name "SAW_LED") (class "Default")
      (node (ref "R12") (pin "2") (pinfunction "2_2") (pintype "passive"))
      (node (ref "SV4") (pin "6") (pinfunction "6_6") (pintype "passive"))
    )
    (net (code "81") (name "SAW_LED_F") (class "Default")
      (node (ref "SAW") (pin "A") (pinfunction "A_A") (pintype "passive"))
      (node (ref "SV7") (pin "6") (pinfunction "6_6") (pintype "passive"))
    )
    (net (code "82") (name "SCLK") (class "Default")
      (node (ref "U3") (pin "9") (pinfunction "9/RX2/PWM_9") (pintype "bidirectional"))
      (node (ref "U4") (pin "2") (pinfunction "DEM/SCLK_2") (pintype "bidirectional"))
    )
    (net (code "83") (name "SDATA") (class "Default")
      (node (ref "U3") (pin "22/A8") (pinfunction "22/A8/T/PWM_22/A8") (pintype "bidirectional"))
      (node (ref "U4") (pin "1") (pinfunction "SDATA_1") (pintype "bidirectional"))
    )
    (net (code "84") (name "SIN_LED") (class "Default")
      (node (ref "R10") (pin "2") (pinfunction "2_2") (pintype "passive"))
      (node (ref "SV4") (pin "8") (pinfunction "8_8") (pintype "passive"))
    )
    (net (code "85") (name "SIN_LED_F") (class "Default")
      (node (ref "SIN") (pin "A") (pinfunction "A_A") (pintype "passive"))
      (node (ref "SV7") (pin "8") (pinfunction "8_8") (pintype "passive"))
    )
    (net (code "86") (name "SQ_LED") (class "Default")
      (node (ref "R11") (pin "2") (pinfunction "2_2") (pintype "passive"))
      (node (ref "SV4") (pin "7") (pinfunction "7_7") (pintype "passive"))
    )
    (net (code "87") (name "SQ_LED_F") (class "Default")
      (node (ref "SQ") (pin "A") (pinfunction "A_A") (pintype "passive"))
      (node (ref "SV7") (pin "7") (pinfunction "7_7") (pintype "passive"))
    )
    (net (code "88") (name "TRI_LED") (class "Default")
      (node (ref "R13") (pin "2") (pinfunction "2_2") (pintype "passive"))
      (node (ref "SV4") (pin "5") (pinfunction "5_5") (pintype "passive"))
    )
    (net (code "89") (name "TRI_LED_F") (class "Default")
      (node (ref "SV7") (pin "5") (pinfunction "5_5") (pintype "passive"))
      (node (ref "TRI") (pin "A") (pinfunction "A_A") (pintype "passive"))
    )
    (net (code "90") (name "WAVESHAPE") (class "Default")
      (node (ref "SV2") (pin "2") (pinfunction "2_2") (pintype "passive"))
      (node (ref "U3") (pin "7") (pinfunction "7/RX3_7") (pintype "bidirectional"))
    )
    (net (code "91") (name "WAVESH_BUT_F") (class "Default")
      (node (ref "SV5") (pin "3") (pinfunction "3_3") (pintype "passive"))
    )
    (net (code "92") (name "WAVE_TRIG_F") (class "Default")
      (node (ref "R18") (pin "1") (pinfunction "1_1") (pintype "passive"))
      (node (ref "SV6") (pin "2") (pinfunction "2_2") (pintype "passive"))
      (node (ref "T2") (pin "3") (pinfunction "C_3") (pintype "passive"))
    )
    (net (code "93") (name "unconnected-(AUDIO-OUT-SWITCH-PadP$2_SWITCH)") (class "Default")
      (node (ref "AUDIO-OUT") (pin "P$2_SWITCH") (pinfunction "SWITCH_P$2_SWITCH") (pintype "passive"))
    )
    (net (code "94") (name "unconnected-(FM_CV-SWITCH-PadP$2_SWITCH)") (class "Default")
      (node (ref "FM_CV") (pin "P$2_SWITCH") (pinfunction "SWITCH_P$2_SWITCH") (pintype "passive"))
    )
    (net (code "95") (name "unconnected-(GATE-OUT-SWITCH-PadP$2_SWITCH)") (class "Default")
      (node (ref "GATE-OUT") (pin "P$2_SWITCH") (pinfunction "SWITCH_P$2_SWITCH") (pintype "passive"))
    )
    (net (code "96") (name "unconnected-(IC3-ON1-Pad1)") (class "Default")
      (node (ref "IC3") (pin "1") (pinfunction "ON1_1") (pintype "passive"))
    )
    (net (code "97") (name "unconnected-(IC3-ON2-Pad5)") (class "Default")
      (node (ref "IC3") (pin "5") (pinfunction "ON2_5") (pintype "passive"))
    )
    (net (code "98") (name "unconnected-(IC3-OPT-Pad8)") (class "Default")
      (node (ref "IC3") (pin "8") (pinfunction "OPT_8") (pintype "passive"))
    )
    (net (code "99") (name "unconnected-(MIDI-IN-SLEEVE-PadP$3_SLEEVE)") (class "Default")
      (node (ref "MIDI-IN") (pin "P$3_SLEEVE") (pinfunction "SLEEVE_P$3_SLEEVE") (pintype "bidirectional"))
    )
    (net (code "100") (name "unconnected-(RATIO_CV-SWITCH-PadP$2_SWITCH)") (class "Default")
      (node (ref "RATIO_CV") (pin "P$2_SWITCH") (pinfunction "SWITCH_P$2_SWITCH") (pintype "passive"))
    )
    (net (code "101") (name "unconnected-(S1-S-Pad1)") (class "Default")
      (node (ref "S1") (pin "1") (pinfunction "S_1") (pintype "passive"))
    )
    (net (code "102") (name "unconnected-(SV3-Pad3)") (class "Default")
      (node (ref "SV3") (pin "3") (pinfunction "3_3") (pintype "passive"))
    )
    (net (code "103") (name "unconnected-(U3-1{slash}TX1{slash}T-Pad1)") (class "Default")
      (node (ref "U3") (pin "1") (pinfunction "1/TX1/T_1") (pintype "bidirectional"))
    )
    (net (code "104") (name "unconnected-(U3-15{slash}A1{slash}T-Pad15{slash}A1)") (class "Default")
      (node (ref "U3") (pin "15/A1") (pinfunction "15/A1/T_15/A1") (pintype "bidirectional"))
    )
    (net (code "105") (name "unconnected-(U3-20{slash}A6{slash}PWM-Pad20{slash}A6)") (class "Default")
      (node (ref "U3") (pin "20/A6") (pinfunction "20/A6/PWM_20/A6") (pintype "bidirectional"))
    )
    (net (code "106") (name "unconnected-(U3-21{slash}A7{slash}PWM-Pad21{slash}A7)") (class "Default")
      (node (ref "U3") (pin "21/A7") (pinfunction "21/A7/PWM_21/A7") (pintype "bidirectional"))
    )
    (net (code "107") (name "unconnected-(U4-AOUTR-Pad5)") (class "Default")
      (node (ref "U4") (pin "5") (pinfunction "AOUTR_5") (pintype "bidirectional"))
    )
    (net (code "108") (name "unconnected-(WAVE-TRIGGER-SWITCH-PadP$2_SWITCH)") (class "Default")
      (node (ref "WAVE-TRIGGER") (pin "P$2_SWITCH") (pinfunction "SWITCH_P$2_SWITCH") (pintype "passive"))
    )
  )
)
